# AC_to_DC.net
KiCad netlist of a schematic drawn in EAGLE
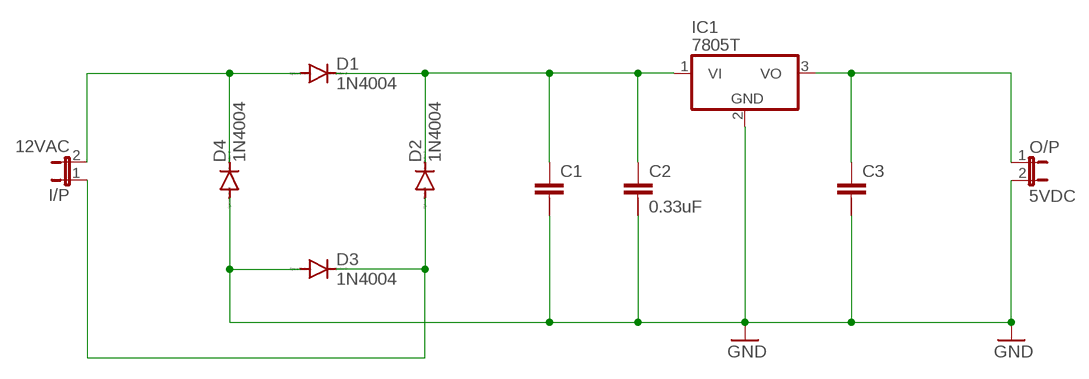
[diagram p0: schematic, sheet 1]

(export (version "E")
  (design (tool "Eeschema 10.0.6"))
  (components
    (comp (ref "C1")
      (value "C-2.5-5/2")
      (footprint "eagle-import:C2.5_5-2")
      (libsource (lib "eagle-import") (part "C-2.5-5/2"))
    )
    (comp (ref "C2")
      (value "0.33uF")
      (footprint "eagle-import:C2.5_5-2")
      (libsource (lib "eagle-import") (part "C-2.5-5/2"))
    )
    (comp (ref "C3")
      (value "C-2.5-5/2")
      (footprint "eagle-import:C2.5_5-2")
      (libsource (lib "eagle-import") (part "C-2.5-5/2"))
    )
    (comp (ref "D1")
      (value "1N4004")
      (footprint "eagle-import:DO41-10")
      (libsource (lib "eagle-import") (part "1N4004"))
    )
    (comp (ref "D2")
      (value "1N4004")
      (footprint "eagle-import:DO41-10")
      (libsource (lib "eagle-import") (part "1N4004"))
    )
    (comp (ref "D3")
      (value "1N4004")
      (footprint "eagle-import:DO41-10")
      (libsource (lib "eagle-import") (part "1N4004"))
    )
    (comp (ref "D4")
      (value "1N4004")
      (footprint "eagle-import:DO41-10")
      (libsource (lib "eagle-import") (part "1N4004"))
    )
    (comp (ref "I/P")
      (value "12VAC")
      (footprint "eagle-import:JP1")
      (libsource (lib "eagle-import") (part "JP1E"))
    )
    (comp (ref "IC1")
      (value "7805T")
      (footprint "eagle-import:TO220H")
      (libsource (lib "eagle-import") (part "78T05"))
    )
    (comp (ref "O/P")
      (value "5VDC")
      (footprint "eagle-import:JP1")
      (libsource (lib "eagle-import") (part "JP1E"))
    )
  )
  (nets
    (net (code "1") (name "GND") (class "Default")
      (node (ref "C1") (pin "2") (pinfunction "2_2") (pintype "passive"))
      (node (ref "C2") (pin "2") (pinfunction "2_2") (pintype "passive"))
      (node (ref "C3") (pin "2") (pinfunction "2_2") (pintype "passive"))
      (node (ref "D3") (pin "A") (pinfunction "A_A") (pintype "passive"))
      (node (ref "D4") (pin "A") (pinfunction "A_A") (pintype "passive"))
      (node (ref "IC1") (pin "2") (pinfunction "GND_2") (pintype "passive"))
      (node (ref "O/P") (pin "2") (pinfunction "2_2") (pintype "passive"))
    )
    (net (code "2") (name "Net-(D1-PadA)") (class "Default")
      (node (ref "D1") (pin "A") (pinfunction "A_A") (pintype "passive"))
      (node (ref "D4") (pin "C") (pinfunction "C_C") (pintype "passive"))
      (node (ref "I/P") (pin "2") (pinfunction "2_2") (pintype "passive"))
    )
    (net (code "3") (name "Net-(D2-PadA)") (class "Default")
      (node (ref "D2") (pin "A") (pinfunction "A_A") (pintype "passive"))
      (node (ref "D3") (pin "C") (pinfunction "C_C") (pintype "passive"))
      (node (ref "I/P") (pin "1") (pinfunction "1_1") (pintype "passive"))
    )
    (net (code "4") (name "Net-(IC1-VI)") (class "Default")
      (node (ref "C1") (pin "1") (pinfunction "1_1") (pintype "passive"))
      (node (ref "C2") (pin "1") (pinfunction "1_1") (pintype "passive"))
      (node (ref "D1") (pin "C") (pinfunction "C_C") (pintype "passive"))
      (node (ref "D2") (pin "C") (pinfunction "C_C") (pintype "passive"))
      (node (ref "IC1") (pin "1") (pinfunction "VI_1") (pintype "input"))
    )
    (net (code "5") (name "Net-(IC1-VO)") (class "Default")
      (node (ref "C3") (pin "1") (pinfunction "1_1") (pintype "passive"))
      (node (ref "IC1") (pin "3") (pinfunction "VO_3") (pintype "passive"))
      (node (ref "O/P") (pin "1") (pinfunction "1_1") (pintype "passive"))
    )
    (net (code "6") (name "unconnected-(C1-Pad3)") (class "Default")
      (node (ref "C1") (pin "3") (pinfunction "3_3") (pintype "passive"))
    )
    (net (code "7") (name "unconnected-(C2-Pad3)") (class "Default")
      (node (ref "C2") (pin "3") (pinfunction "3_3") (pintype "passive"))
    )
    (net (code "8") (name "unconnected-(C3-Pad3)") (class "Default")
      (node (ref "C3") (pin "3") (pinfunction "3_3") (pintype "passive"))
    )
  )
)
